# led-group.net
KiCad netlist of a schematic drawn in Altium Designer
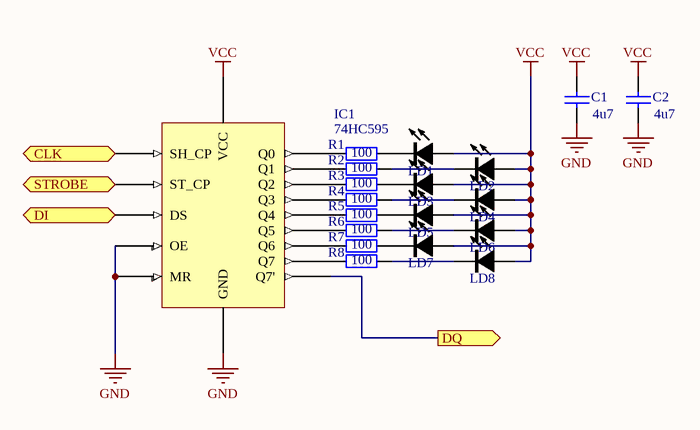
[diagram p0: led-group.SchDoc]

(export (version "E")
  (design (tool "Eeschema 10.0.6"))
  (components
    (comp (ref "C1")
      (value "4u7")
      (footprint "6-0805_M")
      (description "Capacitor")
      (fields (field (name "Comment") "Cap"))
      (libsource (lib "Miscellaneous Devices") (part "Cap"))
    )
    (comp (ref "C2")
      (value "4u7")
      (footprint "6-0805_M")
      (description "Capacitor")
      (fields (field (name "Comment") "Cap"))
      (libsource (lib "Miscellaneous Devices") (part "Cap"))
    )
    (comp (ref "IC1")
      (value "74HC595")
      (footprint "TSSOP16")
      (description "74HC595 8-bit latched SIPO shift register")
      (libsource (lib "Components") (part "Component_1"))
    )
    (comp (ref "LD1") (value "UV-LED") (footprint "0805-LED") (libsource (lib "Components") (part "UV-LED")))
    (comp (ref "LD2") (value "UV-LED") (footprint "0805-LED") (libsource (lib "Components") (part "UV-LED")))
    (comp (ref "LD3") (value "UV-LED") (footprint "0805-LED") (libsource (lib "Components") (part "UV-LED")))
    (comp (ref "LD4") (value "UV-LED") (footprint "0805-LED") (libsource (lib "Components") (part "UV-LED")))
    (comp (ref "LD5") (value "UV-LED") (footprint "0805-LED") (libsource (lib "Components") (part "UV-LED")))
    (comp (ref "LD6") (value "UV-LED") (footprint "0805-LED") (libsource (lib "Components") (part "UV-LED")))
    (comp (ref "LD7") (value "UV-LED") (footprint "0805-LED") (libsource (lib "Components") (part "UV-LED")))
    (comp (ref "LD8") (value "UV-LED") (footprint "0805-LED") (libsource (lib "Components") (part "UV-LED")))
    (comp (ref "R1")
      (value "100")
      (footprint "6-0805_N")
      (description "Resistor")
      (libsource (lib "Miscellaneous Devices") (part "Res2"))
    )
    (comp (ref "R2")
      (value "100")
      (footprint "6-0805_N")
      (description "Resistor")
      (libsource (lib "Miscellaneous Devices") (part "Res2"))
    )
    (comp (ref "R3")
      (value "100")
      (footprint "6-0805_N")
      (description "Resistor")
      (libsource (lib "Miscellaneous Devices") (part "Res2"))
    )
    (comp (ref "R4")
      (value "100")
      (footprint "6-0805_N")
      (description "Resistor")
      (libsource (lib "Miscellaneous Devices") (part "Res2"))
    )
    (comp (ref "R5")
      (value "100")
      (footprint "6-0805_N")
      (description "Resistor")
      (libsource (lib "Miscellaneous Devices") (part "Res2"))
    )
    (comp (ref "R6")
      (value "100")
      (footprint "6-0805_N")
      (description "Resistor")
      (libsource (lib "Miscellaneous Devices") (part "Res2"))
    )
    (comp (ref "R7")
      (value "100")
      (footprint "6-0805_N")
      (description "Resistor")
      (libsource (lib "Miscellaneous Devices") (part "Res2"))
    )
    (comp (ref "R8")
      (value "100")
      (footprint "6-0805_N")
      (description "Resistor")
      (libsource (lib "Miscellaneous Devices") (part "Res2"))
    )
  )
  (nets
    (net (code "1") (name "/CLK") (class "Default")
      (node (ref "IC1") (pin "11") (pinfunction "SH_CP_11") (pintype "input"))
    )
    (net (code "2") (name "/DI") (class "Default")
      (node (ref "IC1") (pin "14") (pinfunction "DS_14") (pintype "input"))
    )
    (net (code "3") (name "/DQ") (class "Default")
      (node (ref "IC1") (pin "9") (pinfunction "Q7'_9") (pintype "output"))
    )
    (net (code "4") (name "/STROBE") (class "Default")
      (node (ref "IC1") (pin "12") (pinfunction "ST_CP_12") (pintype "input"))
    )
    (net (code "5") (name "GND") (class "Default")
      (node (ref "C1") (pin "1") (pinfunction "1_1") (pintype "passive"))
      (node (ref "C2") (pin "1") (pinfunction "1_1") (pintype "passive"))
      (node (ref "IC1") (pin "10") (pinfunction "MR_10") (pintype "input"))
      (node (ref "IC1") (pin "13") (pinfunction "OE_13") (pintype "input"))
      (node (ref "IC1") (pin "8") (pinfunction "GND_8") (pintype "power_in"))
    )
    (net (code "6") (name "Net-(IC1-Q0)") (class "Default")
      (node (ref "IC1") (pin "15") (pinfunction "Q0_15") (pintype "output"))
      (node (ref "R1") (pin "1") (pinfunction "1_1") (pintype "passive"))
    )
    (net (code "7") (name "Net-(IC1-Q1)") (class "Default")
      (node (ref "IC1") (pin "1") (pinfunction "Q1_1") (pintype "output"))
      (node (ref "R2") (pin "1") (pinfunction "1_1") (pintype "passive"))
    )
    (net (code "8") (name "Net-(IC1-Q2)") (class "Default")
      (node (ref "IC1") (pin "2") (pinfunction "Q2_2") (pintype "output"))
      (node (ref "R3") (pin "1") (pinfunction "1_1") (pintype "passive"))
    )
    (net (code "9") (name "Net-(IC1-Q3)") (class "Default")
      (node (ref "IC1") (pin "3") (pinfunction "Q3_3") (pintype "output"))
      (node (ref "R4") (pin "1") (pinfunction "1_1") (pintype "passive"))
    )
    (net (code "10") (name "Net-(IC1-Q4)") (class "Default")
      (node (ref "IC1") (pin "4") (pinfunction "Q4_4") (pintype "output"))
      (node (ref "R5") (pin "1") (pinfunction "1_1") (pintype "passive"))
    )
    (net (code "11") (name "Net-(IC1-Q5)") (class "Default")
      (node (ref "IC1") (pin "5") (pinfunction "Q5_5") (pintype "output"))
      (node (ref "R6") (pin "1") (pinfunction "1_1") (pintype "passive"))
    )
    (net (code "12") (name "Net-(IC1-Q6)") (class "Default")
      (node (ref "IC1") (pin "6") (pinfunction "Q6_6") (pintype "output"))
      (node (ref "R7") (pin "1") (pinfunction "1_1") (pintype "passive"))
    )
    (net (code "13") (name "Net-(IC1-Q7)") (class "Default")
      (node (ref "IC1") (pin "7") (pinfunction "Q7_7") (pintype "output"))
      (node (ref "R8") (pin "1") (pinfunction "1_1") (pintype "passive"))
    )
    (net (code "14") (name "Net-(LD1-PadK)") (class "Default")
      (node (ref "LD1") (pin "K") (pinfunction "K_K") (pintype "passive"))
      (node (ref "R1") (pin "2") (pinfunction "2_2") (pintype "passive"))
    )
    (net (code "15") (name "Net-(LD2-PadK)") (class "Default")
      (node (ref "LD2") (pin "K") (pinfunction "K_K") (pintype "passive"))
      (node (ref "R2") (pin "2") (pinfunction "2_2") (pintype "passive"))
    )
    (net (code "16") (name "Net-(LD3-PadK)") (class "Default")
      (node (ref "LD3") (pin "K") (pinfunction "K_K") (pintype "passive"))
      (node (ref "R3") (pin "2") (pinfunction "2_2") (pintype "passive"))
    )
    (net (code "17") (name "Net-(LD4-PadK)") (class "Default")
      (node (ref "LD4") (pin "K") (pinfunction "K_K") (pintype "passive"))
      (node (ref "R4") (pin "2") (pinfunction "2_2") (pintype "passive"))
    )
    (net (code "18") (name "Net-(LD5-PadK)") (class "Default")
      (node (ref "LD5") (pin "K") (pinfunction "K_K") (pintype "passive"))
      (node (ref "R5") (pin "2") (pinfunction "2_2") (pintype "passive"))
    )
    (net (code "19") (name "Net-(LD6-PadK)") (class "Default")
      (node (ref "LD6") (pin "K") (pinfunction "K_K") (pintype "passive"))
      (node (ref "R6") (pin "2") (pinfunction "2_2") (pintype "passive"))
    )
    (net (code "20") (name "Net-(LD7-PadK)") (class "Default")
      (node (ref "LD7") (pin "K") (pinfunction "K_K") (pintype "passive"))
      (node (ref "R7") (pin "2") (pinfunction "2_2") (pintype "passive"))
    )
    (net (code "21") (name "Net-(LD8-PadK)") (class "Default")
      (node (ref "LD8") (pin "K") (pinfunction "K_K") (pintype "passive"))
      (node (ref "R8") (pin "2") (pinfunction "2_2") (pintype "passive"))
    )
    (net (code "22") (name "VCC") (class "Default")
      (node (ref "C1") (pin "2") (pinfunction "2_2") (pintype "passive"))
      (node (ref "C2") (pin "2") (pinfunction "2_2") (pintype "passive"))
      (node (ref "IC1") (pin "16") (pinfunction "VCC_16") (pintype "power_in"))
      (node (ref "LD1") (pin "A") (pinfunction "A_A") (pintype "passive"))
      (node (ref "LD2") (pin "A") (pinfunction "A_A") (pintype "passive"))
      (node (ref "LD3") (pin "A") (pinfunction "A_A") (pintype "passive"))
      (node (ref "LD4") (pin "A") (pinfunction "A_A") (pintype "passive"))
      (node (ref "LD5") (pin "A") (pinfunction "A_A") (pintype "passive"))
      (node (ref "LD6") (pin "A") (pinfunction "A_A") (pintype "passive"))
      (node (ref "LD7") (pin "A") (pinfunction "A_A") (pintype "passive"))
      (node (ref "LD8") (pin "A") (pinfunction "A_A") (pintype "passive"))
    )
  )
)
